# Schematic_Past.net
KiCad netlist of a schematic drawn in EAGLE
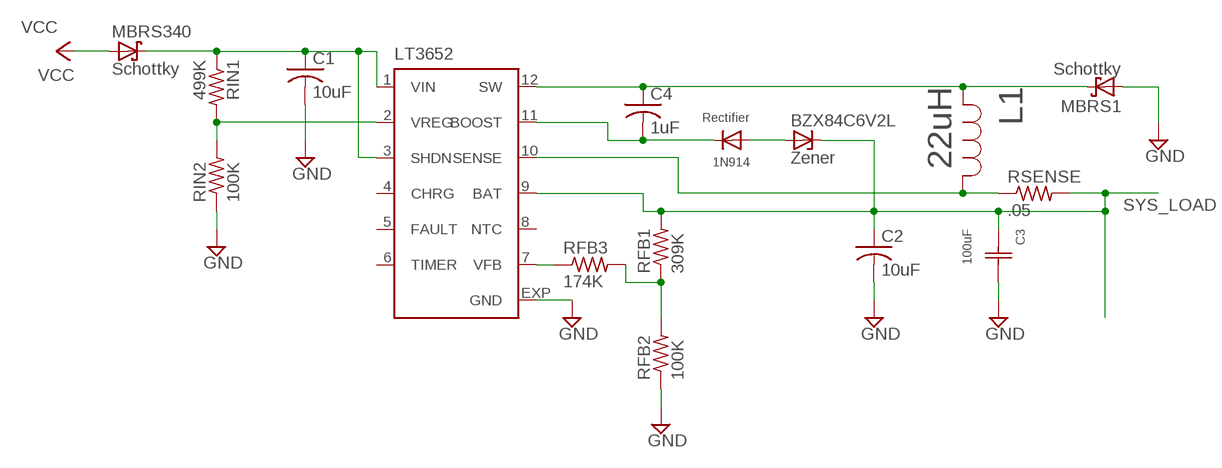
[diagram p0: schematic, sheet 1]

(export (version "E")
  (design (tool "Eeschema 10.0.6"))
  (components
    (comp (ref "1N914")
      (value "Rectifier")
      (footprint "eagle-import:SOD-323F")
      (libsource (lib "eagle-import") (part "DIODESOD-323F"))
    )
    (comp (ref "BZX84C6V2L")
      (value "Zener")
      (footprint "eagle-import:TO236")
      (libsource (lib "eagle-import") (part "ZENER-DIODETO236"))
    )
    (comp (ref "C1")
      (value "10uF")
      (footprint "eagle-import:C0805")
      (libsource (lib "eagle-import") (part "C-USC0805"))
    )
    (comp (ref "C2")
      (value "10uF")
      (footprint "eagle-import:C0805")
      (libsource (lib "eagle-import") (part "C-USC0805"))
    )
    (comp (ref "C3")
      (value "100uF")
      (footprint "eagle-import:CAP_EEFK_E")
      (fields (field (name "MANUFACTURER_PART_NUMBER") "EEETG1E101UP"))
      (libsource (lib "eagle-import") (part "EEETG1E101UP"))
    )
    (comp (ref "C4")
      (value "1uF")
      (footprint "eagle-import:C0805")
      (libsource (lib "eagle-import") (part "C-USC0805"))
    )
    (comp (ref "L1")
      (value "22uH")
      (footprint "eagle-import:IND_BOURNS_SRR1205")
      (fields (field (name "MANUFACTURER_PART_NUMBER") "SRR1205220ML"))
      (libsource (lib "eagle-import") (part "SRR1205-220ML"))
    )
    (comp (ref "LT3652")
      (value "LT3645MSE")
      (footprint "eagle-import:MSOP12")
      (libsource (lib "eagle-import") (part "LT3645MSE"))
    )
    (comp (ref "MBRS1")
      (value "Schottky")
      (footprint "eagle-import:SMC")
      (libsource (lib "eagle-import") (part "SCHOTTKY-DIODESMC"))
    )
    (comp (ref "MBRS340")
      (value "Schottky")
      (footprint "eagle-import:SMC")
      (libsource (lib "eagle-import") (part "SCHOTTKY-DIODESMC"))
    )
    (comp (ref "RFB1")
      (value "309K")
      (footprint "eagle-import:R0603")
      (libsource (lib "eagle-import") (part "R-US_R0603"))
    )
    (comp (ref "RFB2")
      (value "100K")
      (footprint "eagle-import:R0603")
      (libsource (lib "eagle-import") (part "R-US_R0603"))
    )
    (comp (ref "RFB3")
      (value "174K")
      (footprint "eagle-import:R0603")
      (libsource (lib "eagle-import") (part "R-US_R0603"))
    )
    (comp (ref "RIN1")
      (value "499K")
      (footprint "eagle-import:R0603")
      (libsource (lib "eagle-import") (part "R-US_R0603"))
    )
    (comp (ref "RIN2")
      (value "100K")
      (footprint "eagle-import:R0603")
      (libsource (lib "eagle-import") (part "R-US_R0603"))
    )
    (comp (ref "RSENSE")
      (value ".05")
      (footprint "eagle-import:R2512")
      (libsource (lib "eagle-import") (part "R-US_R2512"))
    )
  )
  (nets
    (net (code "1") (name "/SYS_LOAD") (class "Default")
      (node (ref "BZX84C6V2L") (pin "C") (pinfunction "C_C") (pintype "passive"))
      (node (ref "C2") (pin "1") (pinfunction "1_1") (pintype "passive"))
      (node (ref "C3") (pin "1") (pinfunction "11_1") (pintype "passive"))
      (node (ref "LT3652") (pin "9") (pinfunction "BAT_9") (pintype "input"))
      (node (ref "RFB1") (pin "2") (pinfunction "2_2") (pintype "passive"))
      (node (ref "RSENSE") (pin "2") (pinfunction "2_2") (pintype "passive"))
    )
    (net (code "2") (name "GND") (class "Default")
      (node (ref "C1") (pin "2") (pinfunction "2_2") (pintype "passive"))
      (node (ref "C2") (pin "2") (pinfunction "2_2") (pintype "passive"))
      (node (ref "C3") (pin "2") (pinfunction "22_2") (pintype "passive"))
      (node (ref "LT3652") (pin "EXP") (pinfunction "GND_EXP") (pintype "power_in"))
      (node (ref "MBRS1") (pin "A") (pinfunction "A_A") (pintype "passive"))
      (node (ref "RFB2") (pin "1") (pinfunction "1_1") (pintype "passive"))
      (node (ref "RIN2") (pin "1") (pinfunction "1_1") (pintype "passive"))
    )
    (net (code "3") (name "Net-(1N914-PadA)") (class "Default")
      (node (ref "1N914") (pin "A") (pinfunction "A_A") (pintype "passive"))
      (node (ref "BZX84C6V2L") (pin "A") (pinfunction "A_A") (pintype "passive"))
    )
    (net (code "4") (name "Net-(LT3652-BOOST)") (class "Default")
      (node (ref "1N914") (pin "C") (pinfunction "C_C") (pintype "passive"))
      (node (ref "C4") (pin "2") (pinfunction "2_2") (pintype "passive"))
      (node (ref "LT3652") (pin "11") (pinfunction "BOOST_11") (pintype "input"))
    )
    (net (code "5") (name "Net-(LT3652-SENSE)") (class "Default")
      (node (ref "L1") (pin "1") (pinfunction "1_1") (pintype "passive"))
      (node (ref "LT3652") (pin "10") (pinfunction "SENSE_10") (pintype "input"))
      (node (ref "RSENSE") (pin "1") (pinfunction "1_1") (pintype "passive"))
    )
    (net (code "6") (name "Net-(LT3652-SHDN)") (class "Default")
      (node (ref "C1") (pin "1") (pinfunction "1_1") (pintype "passive"))
      (node (ref "LT3652") (pin "1") (pinfunction "VIN_1") (pintype "power_in"))
      (node (ref "LT3652") (pin "3") (pinfunction "SHDN_3") (pintype "input"))
      (node (ref "MBRS340") (pin "C") (pinfunction "C_C") (pintype "passive"))
      (node (ref "RIN1") (pin "1") (pinfunction "1_1") (pintype "passive"))
    )
    (net (code "7") (name "Net-(LT3652-SW)") (class "Default")
      (node (ref "C4") (pin "1") (pinfunction "1_1") (pintype "passive"))
      (node (ref "L1") (pin "2") (pinfunction "2_2") (pintype "passive"))
      (node (ref "LT3652") (pin "12") (pinfunction "SW_12") (pintype "input"))
      (node (ref "MBRS1") (pin "C") (pinfunction "C_C") (pintype "passive"))
    )
    (net (code "8") (name "Net-(LT3652-VFB)") (class "Default")
      (node (ref "LT3652") (pin "7") (pinfunction "VFB_7") (pintype "input"))
      (node (ref "RFB3") (pin "1") (pinfunction "1_1") (pintype "passive"))
    )
    (net (code "9") (name "Net-(LT3652-VREG)") (class "Default")
      (node (ref "LT3652") (pin "2") (pinfunction "VREG_2") (pintype "input"))
      (node (ref "RIN1") (pin "2") (pinfunction "2_2") (pintype "passive"))
      (node (ref "RIN2") (pin "2") (pinfunction "2_2") (pintype "passive"))
    )
    (net (code "10") (name "Net-(RFB1-Pad1)") (class "Default")
      (node (ref "RFB1") (pin "1") (pinfunction "1_1") (pintype "passive"))
      (node (ref "RFB2") (pin "2") (pinfunction "2_2") (pintype "passive"))
      (node (ref "RFB3") (pin "2") (pinfunction "2_2") (pintype "passive"))
    )
    (net (code "11") (name "VCC") (class "Default")
      (node (ref "MBRS340") (pin "A") (pinfunction "A_A") (pintype "passive"))
    )
    (net (code "12") (name "unconnected-(LT3652-CHRG-Pad4)") (class "Default")
      (node (ref "LT3652") (pin "4") (pinfunction "CHRG_4") (pintype "output"))
    )
    (net (code "13") (name "unconnected-(LT3652-FAULT-Pad5)") (class "Default")
      (node (ref "LT3652") (pin "5") (pinfunction "FAULT_5") (pintype "output"))
    )
    (net (code "14") (name "unconnected-(LT3652-NTC-Pad8)") (class "Default")
      (node (ref "LT3652") (pin "8") (pinfunction "NTC_8") (pintype "no_connect"))
    )
    (net (code "15") (name "unconnected-(LT3652-TIMER-Pad6)") (class "Default")
      (node (ref "LT3652") (pin "6") (pinfunction "TIMER_6") (pintype "no_connect"))
    )
  )
)
